# board_diff_-_locked_for_some_reason.net
KiCad netlist of a schematic drawn in EAGLE
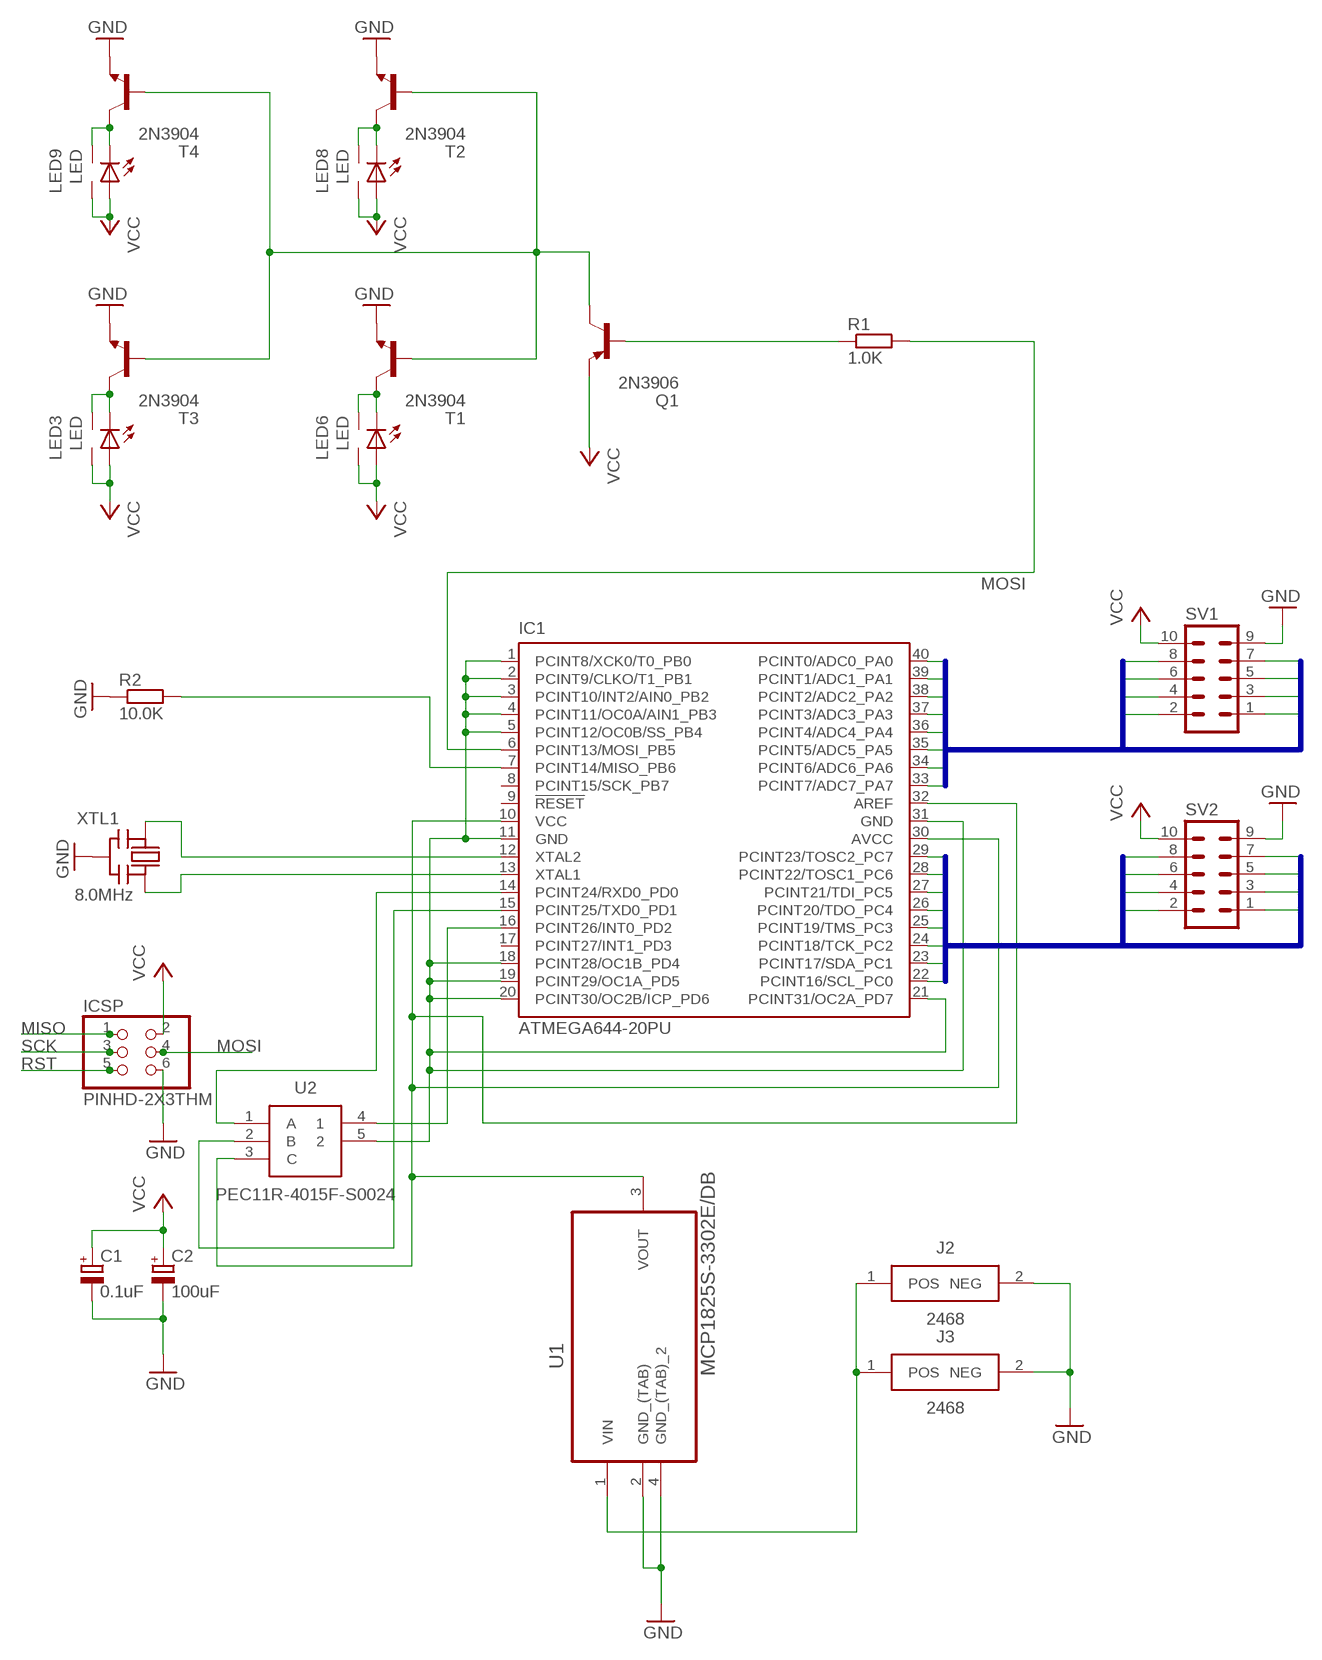
[diagram p0: schematic, sheet 1]

(export (version "E")
  (design (tool "Eeschema 10.0.6"))
  (components
    (comp (ref "C1")
      (value "0.1uF")
      (footprint "eagle-import:E2,5-6E")
      (libsource (lib "eagle-import") (part "CPOL-EUE2,5-6E"))
    )
    (comp (ref "C2")
      (value "100uF")
      (footprint "eagle-import:E2,5-6E")
      (libsource (lib "eagle-import") (part "CPOL-EUE2,5-6E"))
    )
    (comp (ref "IC1")
      (value "ATMEGA644-20PU")
      (footprint "eagle-import:DIL40")
      (libsource (lib "eagle-import") (part "ATMEGA644-PU20"))
    )
    (comp (ref "ICSP")
      (value "PINHD-2X3THM")
      (footprint "eagle-import:ISP6")
      (libsource (lib "eagle-import") (part "PINHD-2X3THM"))
    )
    (comp (ref "J2")
      (value "2468")
      (footprint "eagle-import:2468")
      (fields (field (name "RS_PART_NUMBER") "2794965"))
      (libsource (lib "eagle-import") (part "2468"))
    )
    (comp (ref "J3")
      (value "2468")
      (footprint "eagle-import:2468")
      (fields (field (name "RS_PART_NUMBER") "2794965"))
      (libsource (lib "eagle-import") (part "2468"))
    )
    (comp (ref "LED3")
      (value "LED")
      (footprint "eagle-import:5MM-SIDE")
      (libsource (lib "eagle-import") (part "LED"))
    )
    (comp (ref "LED6")
      (value "LED")
      (footprint "eagle-import:5MM-SIDE")
      (libsource (lib "eagle-import") (part "LED"))
    )
    (comp (ref "LED8")
      (value "LED")
      (footprint "eagle-import:5MM-SIDE")
      (libsource (lib "eagle-import") (part "LED"))
    )
    (comp (ref "LED9")
      (value "LED")
      (footprint "eagle-import:5MM-SIDE")
      (libsource (lib "eagle-import") (part "LED"))
    )
    (comp (ref "Q1")
      (value "2N3906")
      (footprint "eagle-import:TO92")
      (libsource (lib "eagle-import") (part "2N3906"))
    )
    (comp (ref "R1")
      (value "1.0K")
      (footprint "eagle-import:0207_7")
      (libsource (lib "eagle-import") (part "R-EU_0207/7"))
    )
    (comp (ref "R2")
      (value "10.0K")
      (footprint "eagle-import:0207_7")
      (libsource (lib "eagle-import") (part "R-EU_0207/7"))
    )
    (comp (ref "SV1")
      (value "MA05-2")
      (footprint "eagle-import:MA05-2")
      (libsource (lib "eagle-import") (part "MA05-2"))
    )
    (comp (ref "SV2")
      (value "MA05-2")
      (footprint "eagle-import:MA05-2")
      (libsource (lib "eagle-import") (part "MA05-2"))
    )
    (comp (ref "T1")
      (value "2N3904")
      (footprint "eagle-import:TO92")
      (libsource (lib "eagle-import") (part "2N3904"))
    )
    (comp (ref "T2")
      (value "2N3904")
      (footprint "eagle-import:TO92")
      (libsource (lib "eagle-import") (part "2N3904"))
    )
    (comp (ref "T3")
      (value "2N3904")
      (footprint "eagle-import:TO92")
      (libsource (lib "eagle-import") (part "2N3904"))
    )
    (comp (ref "T4")
      (value "2N3904")
      (footprint "eagle-import:TO92")
      (libsource (lib "eagle-import") (part "2N3904"))
    )
    (comp (ref "U1")
      (value "MCP1825S-3302E/DB")
      (footprint "eagle-import:SOT230P700X180-4N")
      (fields (field (name "MF") "Microchip"))
      (libsource (lib "eagle-import") (part "MCP1825S-3302E/DB"))
    )
    (comp (ref "U2")
      (value "PEC11R-4015F-S0024")
      (footprint "eagle-import:PEC12R-4XXXF-SXXXX_1")
      (fields (field (name "RS_PART_NUMBER") "7377739P"))
      (libsource (lib "eagle-import") (part "PEC11R-4015F-S0024"))
    )
    (comp (ref "XTL1")
      (value "8.0MHz")
      (footprint "eagle-import:CERM_OSC")
      (libsource (lib "eagle-import") (part "CERMOSCILL"))
    )
  )
  (nets
    (net (code "1") (name "/MISO") (class "Default")
      (node (ref "ICSP") (pin "1") (pinfunction "1_1") (pintype "passive"))
    )
    (net (code "2") (name "/MOSI") (class "Default")
      (node (ref "IC1") (pin "6") (pinfunction "PCINT13/MOSI_PB5_6") (pintype "bidirectional"))
      (node (ref "ICSP") (pin "4") (pinfunction "4_4") (pintype "passive"))
      (node (ref "R1") (pin "2") (pinfunction "2_2") (pintype "passive"))
    )
    (net (code "3") (name "/PA0") (class "Default")
      (node (ref "IC1") (pin "40") (pinfunction "PCINT0/ADC0_PA0_40") (pintype "bidirectional"))
      (node (ref "SV1") (pin "8") (pinfunction "8_8") (pintype "passive"))
    )
    (net (code "4") (name "/PA1") (class "Default")
      (node (ref "IC1") (pin "39") (pinfunction "PCINT1/ADC1_PA1_39") (pintype "bidirectional"))
      (node (ref "SV1") (pin "6") (pinfunction "6_6") (pintype "passive"))
    )
    (net (code "5") (name "/PA2") (class "Default")
      (node (ref "IC1") (pin "38") (pinfunction "PCINT2/ADC2_PA2_38") (pintype "bidirectional"))
      (node (ref "SV1") (pin "4") (pinfunction "4_4") (pintype "passive"))
    )
    (net (code "6") (name "/PA3") (class "Default")
      (node (ref "IC1") (pin "37") (pinfunction "PCINT3/ADC3_PA3_37") (pintype "bidirectional"))
      (node (ref "SV1") (pin "2") (pinfunction "2_2") (pintype "passive"))
    )
    (net (code "7") (name "/PA4") (class "Default")
      (node (ref "IC1") (pin "36") (pinfunction "PCINT4/ADC4_PA4_36") (pintype "bidirectional"))
      (node (ref "SV1") (pin "1") (pinfunction "1_1") (pintype "passive"))
    )
    (net (code "8") (name "/PA5") (class "Default")
      (node (ref "IC1") (pin "35") (pinfunction "PCINT5/ADC5_PA5_35") (pintype "bidirectional"))
      (node (ref "SV1") (pin "3") (pinfunction "3_3") (pintype "passive"))
    )
    (net (code "9") (name "/PA6") (class "Default")
      (node (ref "IC1") (pin "34") (pinfunction "PCINT6/ADC6_PA6_34") (pintype "bidirectional"))
      (node (ref "SV1") (pin "5") (pinfunction "5_5") (pintype "passive"))
    )
    (net (code "10") (name "/PA7") (class "Default")
      (node (ref "IC1") (pin "33") (pinfunction "PCINT7/ADC7_PA7_33") (pintype "bidirectional"))
      (node (ref "SV1") (pin "7") (pinfunction "7_7") (pintype "passive"))
    )
    (net (code "11") (name "/PC0") (class "Default")
      (node (ref "IC1") (pin "22") (pinfunction "PCINT16/SCL_PC0_22") (pintype "bidirectional"))
      (node (ref "SV2") (pin "8") (pinfunction "8_8") (pintype "passive"))
    )
    (net (code "12") (name "/PC1") (class "Default")
      (node (ref "IC1") (pin "23") (pinfunction "PCINT17/SDA_PC1_23") (pintype "bidirectional"))
      (node (ref "SV2") (pin "6") (pinfunction "6_6") (pintype "passive"))
    )
    (net (code "13") (name "/PC2") (class "Default")
      (node (ref "IC1") (pin "24") (pinfunction "PCINT18/TCK_PC2_24") (pintype "bidirectional"))
      (node (ref "SV2") (pin "4") (pinfunction "4_4") (pintype "passive"))
    )
    (net (code "14") (name "/PC3") (class "Default")
      (node (ref "IC1") (pin "25") (pinfunction "PCINT19/TMS_PC3_25") (pintype "bidirectional"))
      (node (ref "SV2") (pin "2") (pinfunction "2_2") (pintype "passive"))
    )
    (net (code "15") (name "/PC4") (class "Default")
      (node (ref "IC1") (pin "26") (pinfunction "PCINT20/TDO_PC4_26") (pintype "bidirectional"))
      (node (ref "SV2") (pin "1") (pinfunction "1_1") (pintype "passive"))
    )
    (net (code "16") (name "/PC5") (class "Default")
      (node (ref "IC1") (pin "27") (pinfunction "PCINT21/TDI_PC5_27") (pintype "bidirectional"))
      (node (ref "SV2") (pin "3") (pinfunction "3_3") (pintype "passive"))
    )
    (net (code "17") (name "/PC6") (class "Default")
      (node (ref "IC1") (pin "28") (pinfunction "PCINT22/TOSC1_PC6_28") (pintype "bidirectional"))
      (node (ref "SV2") (pin "5") (pinfunction "5_5") (pintype "passive"))
    )
    (net (code "18") (name "/PC7") (class "Default")
      (node (ref "IC1") (pin "29") (pinfunction "PCINT23/TOSC2_PC7_29") (pintype "bidirectional"))
      (node (ref "SV2") (pin "7") (pinfunction "7_7") (pintype "passive"))
    )
    (net (code "19") (name "/RST") (class "Default")
      (node (ref "ICSP") (pin "5") (pinfunction "5_5") (pintype "passive"))
    )
    (net (code "20") (name "/SCK") (class "Default")
      (node (ref "ICSP") (pin "3") (pinfunction "3_3") (pintype "passive"))
    )
    (net (code "21") (name "GND") (class "Default")
      (node (ref "C1") (pin "-") (pinfunction "-_-") (pintype "passive"))
      (node (ref "C2") (pin "-") (pinfunction "-_-") (pintype "passive"))
      (node (ref "ICSP") (pin "6") (pinfunction "6_6") (pintype "passive"))
      (node (ref "J2") (pin "2") (pinfunction "NEG_2") (pintype "passive"))
      (node (ref "J3") (pin "2") (pinfunction "NEG_2") (pintype "passive"))
      (node (ref "R2") (pin "1") (pinfunction "1_1") (pintype "passive"))
      (node (ref "SV1") (pin "9") (pinfunction "9_9") (pintype "passive"))
      (node (ref "SV2") (pin "9") (pinfunction "9_9") (pintype "passive"))
      (node (ref "T1") (pin "3") (pinfunction "E_3") (pintype "passive"))
      (node (ref "T2") (pin "3") (pinfunction "E_3") (pintype "passive"))
      (node (ref "T3") (pin "3") (pinfunction "E_3") (pintype "passive"))
      (node (ref "T4") (pin "3") (pinfunction "E_3") (pintype "passive"))
      (node (ref "U1") (pin "2") (pinfunction "GND_(TAB)_2") (pintype "passive"))
      (node (ref "U1") (pin "4") (pinfunction "GND_(TAB)_2_4") (pintype "passive"))
      (node (ref "XTL1") (pin "P$2") (pinfunction "GND_P$2") (pintype "bidirectional"))
    )
    (net (code "22") (name "Net-(IC1-AREF)") (class "Default")
      (node (ref "IC1") (pin "10") (pinfunction "VCC_10") (pintype "power_in"))
      (node (ref "IC1") (pin "30") (pinfunction "AVCC_30") (pintype "power_in"))
      (node (ref "IC1") (pin "32") (pinfunction "AREF_32") (pintype "passive"))
      (node (ref "U1") (pin "3") (pinfunction "VOUT_3") (pintype "output"))
      (node (ref "U2") (pin "3") (pinfunction "C_3") (pintype "passive"))
    )
    (net (code "23") (name "Net-(IC1-PCINT10{slash}INT2{slash}AIN0_PB2)") (class "Default")
      (node (ref "IC1") (pin "1") (pinfunction "PCINT8/XCK0/T0_PB0_1") (pintype "bidirectional"))
      (node (ref "IC1") (pin "11") (pinfunction "GND_11") (pintype "power_in"))
      (node (ref "IC1") (pin "18") (pinfunction "PCINT28/OC1B_PD4_18") (pintype "bidirectional"))
      (node (ref "IC1") (pin "19") (pinfunction "PCINT29/OC1A_PD5_19") (pintype "bidirectional"))
      (node (ref "IC1") (pin "2") (pinfunction "PCINT9/CLKO/T1_PB1_2") (pintype "bidirectional"))
      (node (ref "IC1") (pin "20") (pinfunction "PCINT30/OC2B/ICP_PD6_20") (pintype "bidirectional"))
      (node (ref "IC1") (pin "21") (pinfunction "PCINT31/OC2A_PD7_21") (pintype "bidirectional"))
      (node (ref "IC1") (pin "3") (pinfunction "PCINT10/INT2/AIN0_PB2_3") (pintype "bidirectional"))
      (node (ref "IC1") (pin "31") (pinfunction "GND_31") (pintype "power_in"))
      (node (ref "IC1") (pin "4") (pinfunction "PCINT11/OC0A/AIN1_PB3_4") (pintype "bidirectional"))
      (node (ref "IC1") (pin "5") (pinfunction "PCINT12/OC0B/SS_PB4_5") (pintype "bidirectional"))
      (node (ref "U2") (pin "5") (pinfunction "2_5") (pintype "passive"))
    )
    (net (code "24") (name "Net-(IC1-PCINT14{slash}MISO_PB6)") (class "Default")
      (node (ref "IC1") (pin "7") (pinfunction "PCINT14/MISO_PB6_7") (pintype "bidirectional"))
      (node (ref "R2") (pin "2") (pinfunction "2_2") (pintype "passive"))
    )
    (net (code "25") (name "Net-(IC1-PCINT24{slash}RXD0_PD0)") (class "Default")
      (node (ref "IC1") (pin "14") (pinfunction "PCINT24/RXD0_PD0_14") (pintype "bidirectional"))
      (node (ref "U2") (pin "1") (pinfunction "A_1") (pintype "passive"))
    )
    (net (code "26") (name "Net-(IC1-PCINT25{slash}TXD0_PD1)") (class "Default")
      (node (ref "IC1") (pin "15") (pinfunction "PCINT25/TXD0_PD1_15") (pintype "bidirectional"))
      (node (ref "U2") (pin "2") (pinfunction "B_2") (pintype "passive"))
    )
    (net (code "27") (name "Net-(IC1-PCINT26{slash}INT0_PD2)") (class "Default")
      (node (ref "IC1") (pin "16") (pinfunction "PCINT26/INT0_PD2_16") (pintype "bidirectional"))
      (node (ref "U2") (pin "4") (pinfunction "1_4") (pintype "passive"))
    )
    (net (code "28") (name "Net-(IC1-XTAL1)") (class "Default")
      (node (ref "IC1") (pin "13") (pinfunction "XTAL1_13") (pintype "input"))
      (node (ref "XTL1") (pin "P$3") (pinfunction "OUT_P$3") (pintype "bidirectional"))
    )
    (net (code "29") (name "Net-(IC1-XTAL2)") (class "Default")
      (node (ref "IC1") (pin "12") (pinfunction "XTAL2_12") (pintype "output"))
      (node (ref "XTL1") (pin "P$1") (pinfunction "IN_P$1") (pintype "bidirectional"))
    )
    (net (code "30") (name "Net-(J2-POS)") (class "Default")
      (node (ref "J2") (pin "1") (pinfunction "POS_1") (pintype "passive"))
      (node (ref "J3") (pin "1") (pinfunction "POS_1") (pintype "passive"))
      (node (ref "U1") (pin "1") (pinfunction "VIN_1") (pintype "input"))
    )
    (net (code "31") (name "Net-(LED3-C)") (class "Default")
      (node (ref "LED3") (pin "K") (pinfunction "C_K") (pintype "passive"))
      (node (ref "LED3") (pin "K2") (pinfunction "C1_K2") (pintype "passive"))
      (node (ref "T3") (pin "1") (pinfunction "C_1") (pintype "passive"))
    )
    (net (code "32") (name "Net-(LED6-C)") (class "Default")
      (node (ref "LED6") (pin "K") (pinfunction "C_K") (pintype "passive"))
      (node (ref "LED6") (pin "K2") (pinfunction "C1_K2") (pintype "passive"))
      (node (ref "T1") (pin "1") (pinfunction "C_1") (pintype "passive"))
    )
    (net (code "33") (name "Net-(LED8-C)") (class "Default")
      (node (ref "LED8") (pin "K") (pinfunction "C_K") (pintype "passive"))
      (node (ref "LED8") (pin "K2") (pinfunction "C1_K2") (pintype "passive"))
      (node (ref "T2") (pin "1") (pinfunction "C_1") (pintype "passive"))
    )
    (net (code "34") (name "Net-(LED9-C)") (class "Default")
      (node (ref "LED9") (pin "K") (pinfunction "C_K") (pintype "passive"))
      (node (ref "LED9") (pin "K2") (pinfunction "C1_K2") (pintype "passive"))
      (node (ref "T4") (pin "1") (pinfunction "C_1") (pintype "passive"))
    )
    (net (code "35") (name "Net-(Q1-B)") (class "Default")
      (node (ref "Q1") (pin "2") (pinfunction "B_2") (pintype "passive"))
      (node (ref "R1") (pin "1") (pinfunction "1_1") (pintype "passive"))
    )
    (net (code "36") (name "Net-(Q1-C)") (class "Default")
      (node (ref "Q1") (pin "1") (pinfunction "C_1") (pintype "passive"))
      (node (ref "T1") (pin "2") (pinfunction "B_2") (pintype "passive"))
      (node (ref "T2") (pin "2") (pinfunction "B_2") (pintype "passive"))
      (node (ref "T3") (pin "2") (pinfunction "B_2") (pintype "passive"))
      (node (ref "T4") (pin "2") (pinfunction "B_2") (pintype "passive"))
    )
    (net (code "37") (name "VCC") (class "Default")
      (node (ref "C1") (pin "+") (pinfunction "+_+") (pintype "passive"))
      (node (ref "C2") (pin "+") (pinfunction "+_+") (pintype "passive"))
      (node (ref "ICSP") (pin "2") (pinfunction "2_2") (pintype "passive"))
      (node (ref "LED3") (pin "A") (pinfunction "A_A") (pintype "passive"))
      (node (ref "LED3") (pin "A2") (pinfunction "A1_A2") (pintype "passive"))
      (node (ref "LED6") (pin "A") (pinfunction "A_A") (pintype "passive"))
      (node (ref "LED6") (pin "A2") (pinfunction "A1_A2") (pintype "passive"))
      (node (ref "LED8") (pin "A") (pinfunction "A_A") (pintype "passive"))
      (node (ref "LED8") (pin "A2") (pinfunction "A1_A2") (pintype "passive"))
      (node (ref "LED9") (pin "A") (pinfunction "A_A") (pintype "passive"))
      (node (ref "LED9") (pin "A2") (pinfunction "A1_A2") (pintype "passive"))
      (node (ref "Q1") (pin "3") (pinfunction "E_3") (pintype "passive"))
      (node (ref "SV1") (pin "10") (pinfunction "10_10") (pintype "passive"))
      (node (ref "SV2") (pin "10") (pinfunction "10_10") (pintype "passive"))
    )
    (net (code "38") (name "unconnected-(IC1-PCINT15{slash}SCK_PB7-Pad8)") (class "Default")
      (node (ref "IC1") (pin "8") (pinfunction "PCINT15/SCK_PB7_8") (pintype "bidirectional"))
    )
    (net (code "39") (name "unconnected-(IC1-PCINT27{slash}INT1_PD3-Pad17)") (class "Default")
      (node (ref "IC1") (pin "17") (pinfunction "PCINT27/INT1_PD3_17") (pintype "bidirectional"))
    )
    (net (code "40") (name "unconnected-(IC1-~{RESET}-Pad9)") (class "Default")
      (node (ref "IC1") (pin "9") (pinfunction "~{RESET}_9") (pintype "input"))
    )
  )
)
